# ap3036b-boost-driver-mk-2_0.net
KiCad netlist of a schematic drawn in EAGLE
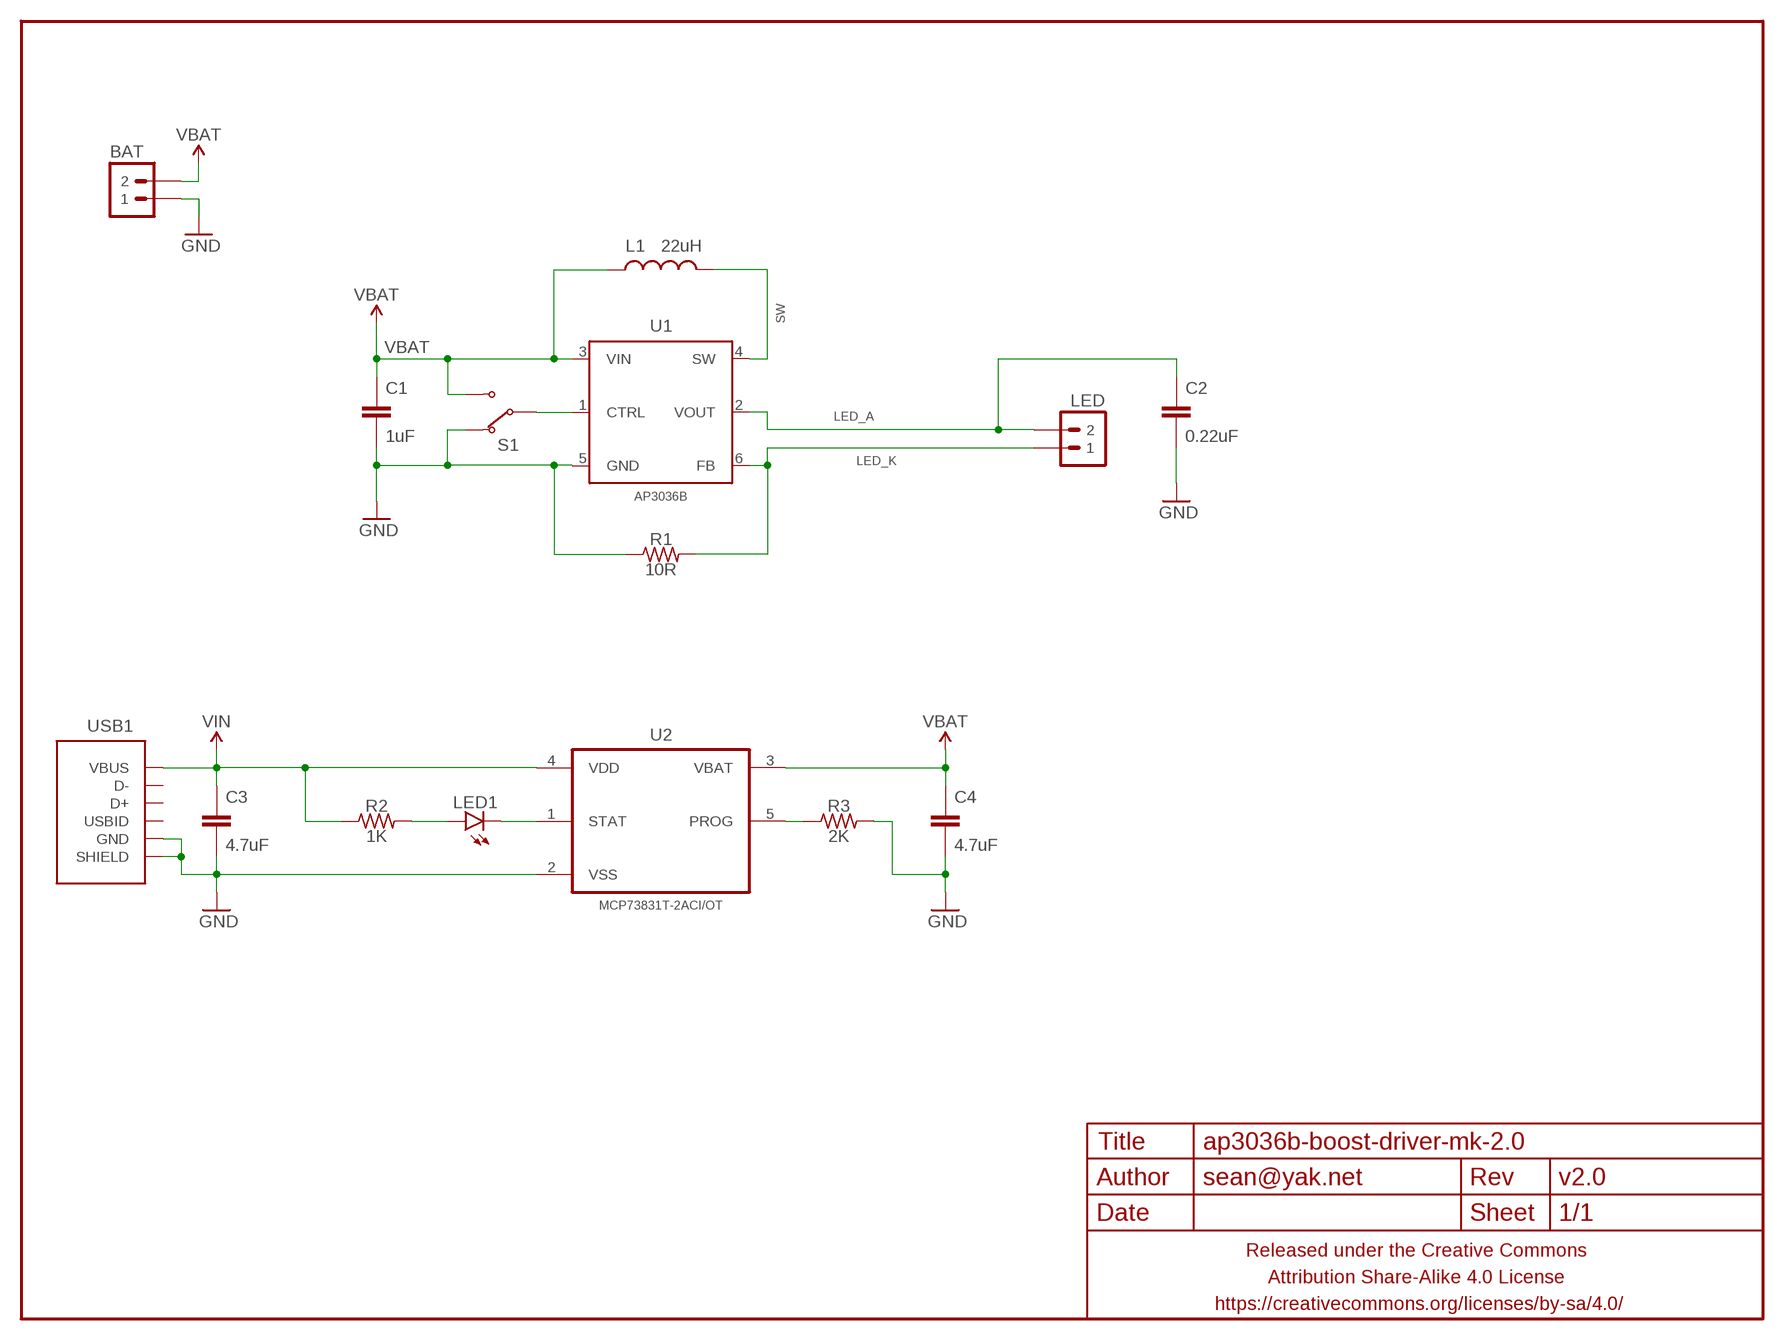
[diagram p0: schematic, sheet 1]

(export (version "E")
  (design (tool "Eeschema 10.0.6"))
  (components
    (comp (ref "BAT")
      (value "M02PTH-CENTERED")
      (footprint "eagle-import:1X02-CENTER")
      (libsource (lib "eagle-import") (part "M02PTH-CENTERED"))
    )
    (comp (ref "C1")
      (value "1uF")
      (footprint "eagle-import:C0603-TIGHTER")
      (libsource (lib "eagle-import") (part "CAPACITOR-CERAMICC0603-TIGHTER"))
    )
    (comp (ref "C2")
      (value "0.22uF")
      (footprint "eagle-import:C0603-TIGHTER")
      (libsource (lib "eagle-import") (part "CAPACITOR-CERAMICC0603-TIGHTER"))
    )
    (comp (ref "C3")
      (value "4.7uF")
      (footprint "eagle-import:C0603-TIGHTER")
      (libsource (lib "eagle-import") (part "CAPACITOR-CERAMICC0603-TIGHTER"))
    )
    (comp (ref "C4")
      (value "4.7uF")
      (footprint "eagle-import:C0603-TIGHTER")
      (libsource (lib "eagle-import") (part "CAPACITOR-CERAMICC0603-TIGHTER"))
    )
    (comp (ref "FRAME1")
      (value "FRAME-LETTERNO_PACKAGE")
      (footprint "eagle-import:DUMMY")
      (fields (field (name "DESIGNER") "sean@yak.net") (field (name "VERSION") "v2.0"))
      (libsource (lib "eagle-import") (part "FRAME-LETTERNO_PACKAGE"))
    )
    (comp (ref "L1")
      (value "22uH")
      (footprint "eagle-import:L0603")
      (libsource (lib "eagle-import") (part "INDUCTOR0603-TIGHTER"))
    )
    (comp (ref "LED")
      (value "M02PTH-CENTERED")
      (footprint "eagle-import:1X02-CENTER")
      (libsource (lib "eagle-import") (part "M02PTH-CENTERED"))
    )
    (comp (ref "LED1")
      (value "LED0603-TIGHT")
      (footprint "eagle-import:LED-0603-TIGHT")
      (libsource (lib "eagle-import") (part "LED0603-TIGHT"))
    )
    (comp (ref "R1")
      (value "10R")
      (footprint "eagle-import:R0603-TIGHTER")
      (libsource (lib "eagle-import") (part "RESISTORR0603-TIGHTER"))
    )
    (comp (ref "R2")
      (value "1K")
      (footprint "eagle-import:R0603-TIGHTER")
      (libsource (lib "eagle-import") (part "RESISTORR0603-TIGHTER"))
    )
    (comp (ref "R3")
      (value "2K")
      (footprint "eagle-import:R0603-TIGHTER")
      (libsource (lib "eagle-import") (part "RESISTORR0603-TIGHTER"))
    )
    (comp (ref "S1")
      (value "SWITCH-SPDTJS102011SAQN")
      (footprint "eagle-import:SWITCH-SPDT-SMD-RA-JS102011SAQN")
      (libsource (lib "eagle-import") (part "SWITCH-SPDTJS102011SAQN"))
    )
    (comp (ref "U1")
      (value "AP3036B")
      (footprint "eagle-import:SOT26")
      (libsource (lib "eagle-import") (part "AP3036B"))
    )
    (comp (ref "U2")
      (value "MCP73831T-2ACI/OT")
      (footprint "eagle-import:SOT95P280X145-5N")
      (libsource (lib "eagle-import") (part "MCP73831T-2ACI/OT"))
    )
    (comp (ref "USB1")
      (value "USB-AB-SHIELDFCI-10118193-USB-MICRO-B")
      (footprint "eagle-import:FCI-10118193-USB-MICRO-B")
      (libsource (lib "eagle-import") (part "USB-AB-SHIELDFCI-10118193-USB-MICRO-B"))
    )
  )
  (nets
    (net (code "1") (name "/LED_A") (class "Default")
      (node (ref "C2") (pin "1") (pinfunction "1_1") (pintype "passive"))
      (node (ref "LED") (pin "2") (pinfunction "2_2") (pintype "passive"))
      (node (ref "U1") (pin "2") (pinfunction "VOUT_2") (pintype "bidirectional"))
    )
    (net (code "2") (name "/LED_K") (class "Default")
      (node (ref "LED") (pin "1") (pinfunction "1_1") (pintype "passive"))
      (node (ref "R1") (pin "2") (pinfunction "2_2") (pintype "passive"))
      (node (ref "U1") (pin "6") (pinfunction "FB_6") (pintype "bidirectional"))
    )
    (net (code "3") (name "/SW") (class "Default")
      (node (ref "L1") (pin "2") (pinfunction "2_2") (pintype "passive"))
      (node (ref "U1") (pin "4") (pinfunction "SW_4") (pintype "bidirectional"))
    )
    (net (code "4") (name "GND") (class "Default")
      (node (ref "BAT") (pin "1") (pinfunction "1_1") (pintype "passive"))
      (node (ref "C1") (pin "2") (pinfunction "2_2") (pintype "passive"))
      (node (ref "C2") (pin "2") (pinfunction "2_2") (pintype "passive"))
      (node (ref "C3") (pin "2") (pinfunction "2_2") (pintype "passive"))
      (node (ref "C4") (pin "2") (pinfunction "2_2") (pintype "passive"))
      (node (ref "R1") (pin "1") (pinfunction "1_1") (pintype "passive"))
      (node (ref "R3") (pin "2") (pinfunction "2_2") (pintype "passive"))
      (node (ref "S1") (pin "3") (pinfunction "NC_3") (pintype "passive"))
      (node (ref "U1") (pin "5") (pinfunction "GND_5") (pintype "bidirectional"))
      (node (ref "U2") (pin "2") (pinfunction "VSS_2") (pintype "power_in"))
      (node (ref "USB1") (pin "5") (pinfunction "GND_5") (pintype "bidirectional"))
      (node (ref "USB1") (pin "SHIELD@1") (pinfunction "SHIELD_SHIELD@1") (pintype "bidirectional"))
      (node (ref "USB1") (pin "SHIELD@2") (pinfunction "SHIELD_SHIELD@2") (pintype "bidirectional"))
      (node (ref "USB1") (pin "SHIELD@3") (pinfunction "SHIELD_SHIELD@3") (pintype "bidirectional"))
      (node (ref "USB1") (pin "SHIELD@4") (pinfunction "SHIELD_SHIELD@4") (pintype "bidirectional"))
    )
    (net (code "5") (name "Net-(LED1-PadA)") (class "Default")
      (node (ref "LED1") (pin "A") (pinfunction "A_A") (pintype "passive"))
      (node (ref "R2") (pin "2") (pinfunction "2_2") (pintype "passive"))
    )
    (net (code "6") (name "Net-(S1-COM)") (class "Default")
      (node (ref "S1") (pin "2") (pinfunction "COM_2") (pintype "passive"))
      (node (ref "U1") (pin "1") (pinfunction "CTRL_1") (pintype "bidirectional"))
    )
    (net (code "7") (name "Net-(U2-PROG)") (class "Default")
      (node (ref "R3") (pin "1") (pinfunction "1_1") (pintype "passive"))
      (node (ref "U2") (pin "5") (pinfunction "PROG_5") (pintype "input"))
    )
    (net (code "8") (name "Net-(U2-STAT)") (class "Default")
      (node (ref "LED1") (pin "C") (pinfunction "C_C") (pintype "passive"))
      (node (ref "U2") (pin "1") (pinfunction "STAT_1") (pintype "output"))
    )
    (net (code "9") (name "VBAT") (class "Default")
      (node (ref "BAT") (pin "2") (pinfunction "2_2") (pintype "passive"))
      (node (ref "C1") (pin "1") (pinfunction "1_1") (pintype "passive"))
      (node (ref "C4") (pin "1") (pinfunction "1_1") (pintype "passive"))
      (node (ref "L1") (pin "1") (pinfunction "1_1") (pintype "passive"))
      (node (ref "S1") (pin "1") (pinfunction "NO_1") (pintype "passive"))
      (node (ref "U1") (pin "3") (pinfunction "VIN_3") (pintype "bidirectional"))
      (node (ref "U2") (pin "3") (pinfunction "VBAT_3") (pintype "output"))
    )
    (net (code "10") (name "VIN") (class "Default")
      (node (ref "C3") (pin "1") (pinfunction "1_1") (pintype "passive"))
      (node (ref "R2") (pin "1") (pinfunction "1_1") (pintype "passive"))
      (node (ref "U2") (pin "4") (pinfunction "VDD_4") (pintype "power_in"))
      (node (ref "USB1") (pin "1") (pinfunction "VBUS_1") (pintype "bidirectional"))
    )
    (net (code "11") (name "unconnected-(USB1-D+-Pad3)") (class "Default")
      (node (ref "USB1") (pin "3") (pinfunction "D+_3") (pintype "bidirectional"))
    )
    (net (code "12") (name "unconnected-(USB1-D--Pad2)") (class "Default")
      (node (ref "USB1") (pin "2") (pinfunction "D-_2") (pintype "bidirectional"))
    )
    (net (code "13") (name "unconnected-(USB1-USBID-Pad4)") (class "Default")
      (node (ref "USB1") (pin "4") (pinfunction "USBID_4") (pintype "bidirectional"))
    )
  )
)
